# MCU.net
KiCad netlist of a schematic drawn in Altium Designer
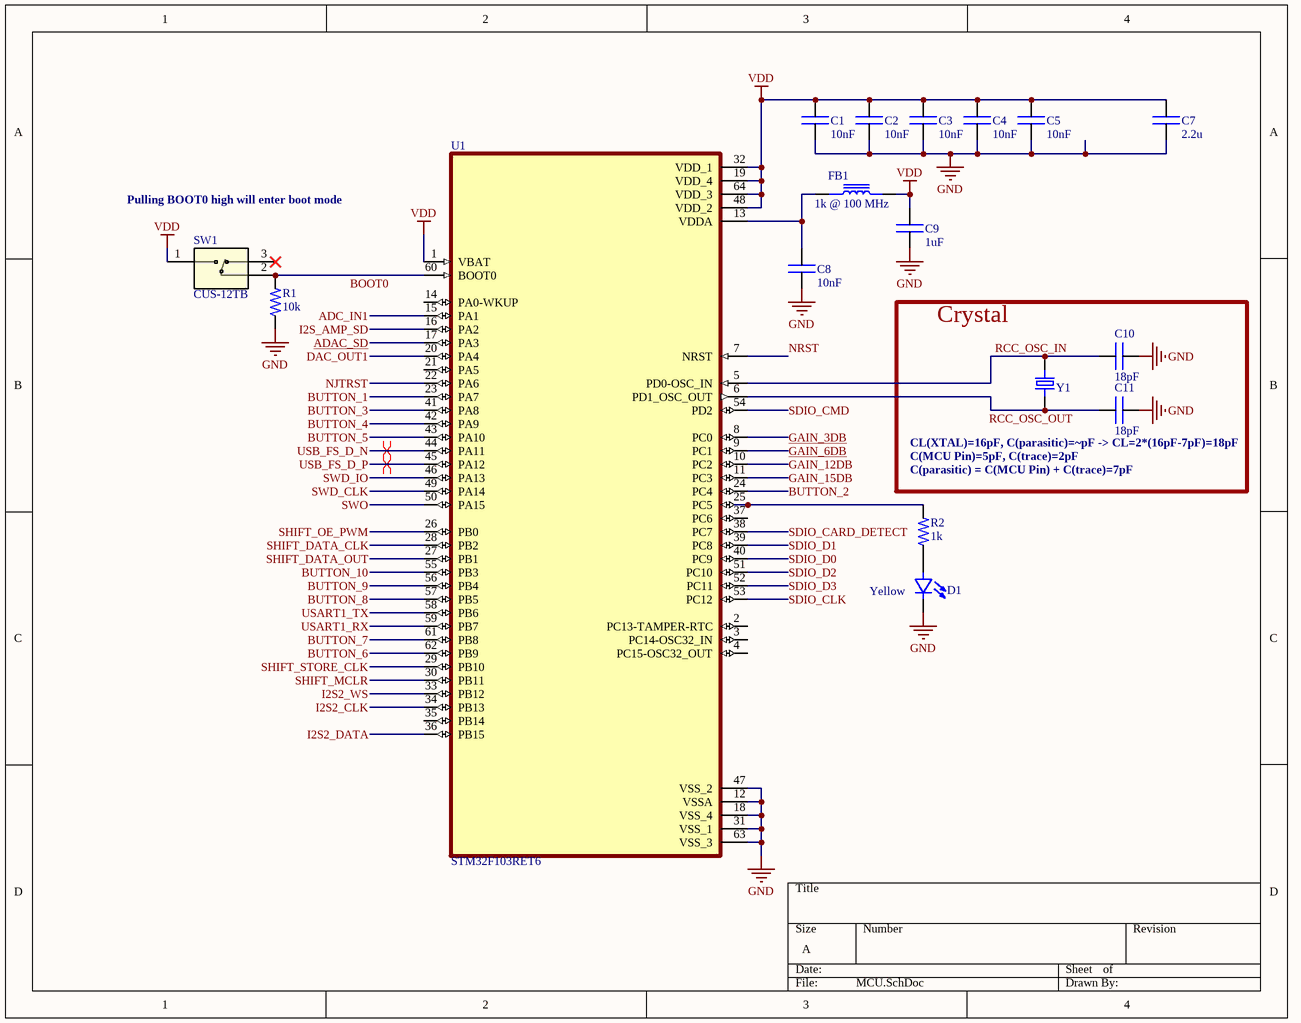
[diagram p0: MCU.SchDoc]

(export (version "E")
  (design (tool "Eeschema 10.0.6"))
  (components
    (comp (ref "C1")
      (value "10nF")
      (footprint "Christmas-2023_Soundboard:0603-CAP")
      (description "Capaicitor")
      (fields (field (name "Comment") "CAP"))
      (libsource (lib "Christmas-2023_Soundboard") (part "CAP"))
    )
    (comp (ref "C2")
      (value "10nF")
      (footprint "Christmas-2023_Soundboard:0603-CAP")
      (description "Capaicitor")
      (fields (field (name "Comment") "CAP"))
      (libsource (lib "Christmas-2023_Soundboard") (part "CAP"))
    )
    (comp (ref "C3")
      (value "10nF")
      (footprint "Christmas-2023_Soundboard:0603-CAP")
      (description "Capaicitor")
      (fields (field (name "Comment") "CAP"))
      (libsource (lib "Christmas-2023_Soundboard") (part "CAP"))
    )
    (comp (ref "C4")
      (value "10nF")
      (footprint "Christmas-2023_Soundboard:0603-CAP")
      (description "Capaicitor")
      (fields (field (name "Comment") "CAP"))
      (libsource (lib "Christmas-2023_Soundboard") (part "CAP"))
    )
    (comp (ref "C5")
      (value "10nF")
      (footprint "Christmas-2023_Soundboard:0603-CAP")
      (description "Capaicitor")
      (fields (field (name "Comment") "CAP"))
      (libsource (lib "Christmas-2023_Soundboard") (part "CAP"))
    )
    (comp (ref "C7")
      (value "2.2u")
      (footprint "Christmas-2023_Soundboard:0603-CAP")
      (description "Capaicitor")
      (fields (field (name "Comment") "CAP"))
      (libsource (lib "Christmas-2023_Soundboard") (part "CAP"))
    )
    (comp (ref "C8")
      (value "10nF")
      (footprint "Christmas-2023_Soundboard:0603-CAP")
      (description "Capaicitor")
      (fields (field (name "Comment") "CAP"))
      (libsource (lib "Christmas-2023_Soundboard") (part "CAP"))
    )
    (comp (ref "C9")
      (value "1uF")
      (footprint "Christmas-2023_Soundboard:0603-CAP")
      (description "Capaicitor")
      (fields (field (name "Comment") "CAP"))
      (libsource (lib "Christmas-2023_Soundboard") (part "CAP"))
    )
    (comp (ref "C10")
      (value "18pF")
      (footprint "Christmas-2023_Soundboard:0603-CAP")
      (description "Capaicitor")
      (fields (field (name "Comment") "CAP"))
      (libsource (lib "Christmas-2023_Soundboard") (part "CAP"))
    )
    (comp (ref "C11")
      (value "18pF")
      (footprint "Christmas-2023_Soundboard:0603-CAP")
      (description "Capaicitor")
      (fields (field (name "Comment") "CAP"))
      (libsource (lib "Christmas-2023_Soundboard") (part "CAP"))
    )
    (comp (ref "D1")
      (value "LED - single")
      (footprint "Christmas-2023_Soundboard:0603-LED")
      (description "LED")
      (fields (field (name "COLOR") "Yellow") (field (name "MFR") "MEIHUA"))
      (libsource (lib "Christmas-2023_Soundboard") (part "LED - single"))
    )
    (comp (ref "FB1")
      (value "1k @ 100 MHz")
      (footprint "Christmas-2023_Soundboard:0603-FB")
      (fields (field (name "MFR") "TDK"))
      (libsource (lib "Christmas-2023_Soundboard") (part "FERRITE BEAD"))
    )
    (comp (ref "R1")
      (value "10k")
      (footprint "Christmas-2023_Soundboard:0603-RES")
      (description "Resistor")
      (fields (field (name "Comment") "RES"))
      (libsource (lib "Christmas-2023_Soundboard") (part "RES"))
    )
    (comp (ref "R2")
      (value "1k")
      (footprint "Christmas-2023_Soundboard:0603-RES")
      (description "Resistor")
      (fields (field (name "Comment") "RES"))
      (libsource (lib "Christmas-2023_Soundboard") (part "RES"))
    )
    (comp (ref "SW1")
      (value "CUS-12TB")
      (footprint "Christmas-2023_Soundboard:SSSS811101")
      (description "JLC Alternate:\r\nSSSS811101")
      (fields (field (name "MFR") "ALPSALPINE"))
      (libsource (lib "Christmas-2023_Soundboard") (part "SPDT SLIDE SWITCH"))
    )
    (comp (ref "U1")
      (value "STM32F103RET6")
      (footprint "Christmas-2023_Soundboard:LQFP-64")
      (fields (field (name "MFR") "STMicroelectronics"))
      (libsource (lib "Christmas-2023_Soundboard") (part "STM32F103RET6"))
    )
    (comp (ref "Y1")
      (value "SX5B12.000F1620F30")
      (footprint "Christmas-2023_Soundboard:SMD5032-4P")
      (description "SMD Tuning Fork Crystal")
      (fields (field (name "MFR") "Shenzhen SCTF Elec"))
      (libsource (lib "Christmas-2023_Soundboard") (part "XTAL-OSC_JLC"))
    )
  )
  (nets
    (net (code "1") (name "/ADAC_SD") (class "Default")
      (node (ref "U1") (pin "17") (pinfunction "PA3_17") (pintype "bidirectional"))
    )
    (net (code "2") (name "/ADC_IN1") (class "Default")
      (node (ref "U1") (pin "15") (pinfunction "PA1_15") (pintype "bidirectional"))
    )
    (net (code "3") (name "/BOOT0") (class "Default")
      (node (ref "R1") (pin "2") (pinfunction "2_2") (pintype "passive"))
      (node (ref "SW1") (pin "2") (pinfunction "2_2") (pintype "passive"))
      (node (ref "U1") (pin "60") (pinfunction "BOOT0_60") (pintype "input"))
    )
    (net (code "4") (name "/BUTTON_1") (class "Default")
      (node (ref "U1") (pin "23") (pinfunction "PA7_23") (pintype "bidirectional"))
    )
    (net (code "5") (name "/BUTTON_2") (class "Default")
      (node (ref "U1") (pin "24") (pinfunction "PC4_24") (pintype "bidirectional"))
    )
    (net (code "6") (name "/BUTTON_3") (class "Default")
      (node (ref "U1") (pin "41") (pinfunction "PA8_41") (pintype "bidirectional"))
    )
    (net (code "7") (name "/BUTTON_4") (class "Default")
      (node (ref "U1") (pin "42") (pinfunction "PA9_42") (pintype "bidirectional"))
    )
    (net (code "8") (name "/BUTTON_5") (class "Default")
      (node (ref "U1") (pin "43") (pinfunction "PA10_43") (pintype "bidirectional"))
    )
    (net (code "9") (name "/BUTTON_6") (class "Default")
      (node (ref "U1") (pin "62") (pinfunction "PB9_62") (pintype "bidirectional"))
    )
    (net (code "10") (name "/BUTTON_7") (class "Default")
      (node (ref "U1") (pin "61") (pinfunction "PB8_61") (pintype "bidirectional"))
    )
    (net (code "11") (name "/BUTTON_8") (class "Default")
      (node (ref "U1") (pin "57") (pinfunction "PB5_57") (pintype "bidirectional"))
    )
    (net (code "12") (name "/BUTTON_9") (class "Default")
      (node (ref "U1") (pin "56") (pinfunction "PB4_56") (pintype "bidirectional"))
    )
    (net (code "13") (name "/BUTTON_10") (class "Default")
      (node (ref "U1") (pin "55") (pinfunction "PB3_55") (pintype "bidirectional"))
    )
    (net (code "14") (name "/DAC_OUT1") (class "Default")
      (node (ref "U1") (pin "20") (pinfunction "PA4_20") (pintype "bidirectional"))
    )
    (net (code "15") (name "/GAIN_3DB") (class "Default")
      (node (ref "U1") (pin "8") (pinfunction "PC0_8") (pintype "bidirectional"))
    )
    (net (code "16") (name "/GAIN_6DB") (class "Default")
      (node (ref "U1") (pin "9") (pinfunction "PC1_9") (pintype "bidirectional"))
    )
    (net (code "17") (name "/GAIN_12DB") (class "Default")
      (node (ref "U1") (pin "10") (pinfunction "PC2_10") (pintype "bidirectional"))
    )
    (net (code "18") (name "/GAIN_15DB") (class "Default")
      (node (ref "U1") (pin "11") (pinfunction "PC3_11") (pintype "bidirectional"))
    )
    (net (code "19") (name "/I2S2_CLK") (class "Default")
      (node (ref "U1") (pin "34") (pinfunction "PB13_34") (pintype "bidirectional"))
    )
    (net (code "20") (name "/I2S2_DATA") (class "Default")
      (node (ref "U1") (pin "36") (pinfunction "PB15_36") (pintype "bidirectional"))
    )
    (net (code "21") (name "/I2S2_WS") (class "Default")
      (node (ref "U1") (pin "33") (pinfunction "PB12_33") (pintype "bidirectional"))
    )
    (net (code "22") (name "/I2S_AMP_SD") (class "Default")
      (node (ref "U1") (pin "16") (pinfunction "PA2_16") (pintype "bidirectional"))
    )
    (net (code "23") (name "/NJTRST") (class "Default")
      (node (ref "U1") (pin "22") (pinfunction "PA6_22") (pintype "bidirectional"))
    )
    (net (code "24") (name "/NRST") (class "Default")
      (node (ref "U1") (pin "7") (pinfunction "NRST_7") (pintype "input"))
    )
    (net (code "25") (name "/RCC_OSC_IN") (class "Default")
      (node (ref "C10") (pin "1") (pinfunction "1_1") (pintype "passive"))
      (node (ref "U1") (pin "5") (pinfunction "PD0-OSC_IN_5") (pintype "input"))
      (node (ref "Y1") (pin "1") (pinfunction "1_1") (pintype "passive"))
    )
    (net (code "26") (name "/RCC_OSC_OUT") (class "Default")
      (node (ref "C11") (pin "1") (pinfunction "1_1") (pintype "passive"))
      (node (ref "U1") (pin "6") (pinfunction "PD1_OSC_OUT_6") (pintype "output"))
      (node (ref "Y1") (pin "2") (pinfunction "2_2") (pintype "passive"))
    )
    (net (code "27") (name "/SDIO_CARD_DETECT") (class "Default")
      (node (ref "U1") (pin "38") (pinfunction "PC7_38") (pintype "bidirectional"))
    )
    (net (code "28") (name "/SDIO_CLK") (class "Default")
      (node (ref "U1") (pin "53") (pinfunction "PC12_53") (pintype "bidirectional"))
    )
    (net (code "29") (name "/SDIO_CMD") (class "Default")
      (node (ref "U1") (pin "54") (pinfunction "PD2_54") (pintype "bidirectional"))
    )
    (net (code "30") (name "/SDIO_D0") (class "Default")
      (node (ref "U1") (pin "40") (pinfunction "PC9_40") (pintype "bidirectional"))
    )
    (net (code "31") (name "/SDIO_D1") (class "Default")
      (node (ref "U1") (pin "39") (pinfunction "PC8_39") (pintype "bidirectional"))
    )
    (net (code "32") (name "/SDIO_D2") (class "Default")
      (node (ref "U1") (pin "51") (pinfunction "PC10_51") (pintype "bidirectional"))
    )
    (net (code "33") (name "/SDIO_D3") (class "Default")
      (node (ref "U1") (pin "52") (pinfunction "PC11_52") (pintype "bidirectional"))
    )
    (net (code "34") (name "/SHIFT_DATA_CLK") (class "Default")
      (node (ref "U1") (pin "28") (pinfunction "PB2_28") (pintype "bidirectional"))
    )
    (net (code "35") (name "/SHIFT_DATA_OUT") (class "Default")
      (node (ref "U1") (pin "27") (pinfunction "PB1_27") (pintype "bidirectional"))
    )
    (net (code "36") (name "/SHIFT_MCLR") (class "Default")
      (node (ref "U1") (pin "30") (pinfunction "PB11_30") (pintype "bidirectional"))
    )
    (net (code "37") (name "/SHIFT_OE_PWM") (class "Default")
      (node (ref "U1") (pin "26") (pinfunction "PB0_26") (pintype "bidirectional"))
    )
    (net (code "38") (name "/SHIFT_STORE_CLK") (class "Default")
      (node (ref "U1") (pin "29") (pinfunction "PB10_29") (pintype "bidirectional"))
    )
    (net (code "39") (name "/SWD_CLK") (class "Default")
      (node (ref "U1") (pin "49") (pinfunction "PA14_49") (pintype "bidirectional"))
    )
    (net (code "40") (name "/SWD_IO") (class "Default")
      (node (ref "U1") (pin "46") (pinfunction "PA13_46") (pintype "bidirectional"))
    )
    (net (code "41") (name "/SWO") (class "Default")
      (node (ref "U1") (pin "50") (pinfunction "PA15_50") (pintype "bidirectional"))
    )
    (net (code "42") (name "/USART1_RX") (class "Default")
      (node (ref "U1") (pin "59") (pinfunction "PB7_59") (pintype "bidirectional"))
    )
    (net (code "43") (name "/USART1_TX") (class "Default")
      (node (ref "U1") (pin "58") (pinfunction "PB6_58") (pintype "bidirectional"))
    )
    (net (code "44") (name "/USB_FS_D_N") (class "Default")
      (node (ref "U1") (pin "44") (pinfunction "PA11_44") (pintype "bidirectional"))
    )
    (net (code "45") (name "/USB_FS_D_P") (class "Default")
      (node (ref "U1") (pin "45") (pinfunction "PA12_45") (pintype "bidirectional"))
    )
    (net (code "46") (name "GND") (class "Default")
      (node (ref "C1") (pin "1") (pinfunction "1_1") (pintype "passive"))
      (node (ref "C10") (pin "2") (pinfunction "2_2") (pintype "passive"))
      (node (ref "C11") (pin "2") (pinfunction "2_2") (pintype "passive"))
      (node (ref "C2") (pin "1") (pinfunction "1_1") (pintype "passive"))
      (node (ref "C3") (pin "1") (pinfunction "1_1") (pintype "passive"))
      (node (ref "C4") (pin "1") (pinfunction "1_1") (pintype "passive"))
      (node (ref "C5") (pin "1") (pinfunction "1_1") (pintype "passive"))
      (node (ref "C7") (pin "1") (pinfunction "1_1") (pintype "passive"))
      (node (ref "C8") (pin "1") (pinfunction "1_1") (pintype "passive"))
      (node (ref "C9") (pin "1") (pinfunction "1_1") (pintype "passive"))
      (node (ref "D1") (pin "2") (pinfunction "C_2") (pintype "passive"))
      (node (ref "R1") (pin "1") (pinfunction "1_1") (pintype "passive"))
      (node (ref "U1") (pin "12") (pinfunction "VSSA_12") (pintype "power_in"))
      (node (ref "U1") (pin "18") (pinfunction "VSS_4_18") (pintype "power_in"))
      (node (ref "U1") (pin "31") (pinfunction "VSS_1_31") (pintype "power_in"))
      (node (ref "U1") (pin "47") (pinfunction "VSS_2_47") (pintype "power_in"))
      (node (ref "U1") (pin "63") (pinfunction "VSS_3_63") (pintype "power_in"))
    )
    (net (code "47") (name "Net-(D1-A)") (class "Default")
      (node (ref "D1") (pin "1") (pinfunction "A_1") (pintype "passive"))
      (node (ref "R2") (pin "1") (pinfunction "1_1") (pintype "passive"))
    )
    (net (code "48") (name "Net-(U1-PC5)") (class "Default")
      (node (ref "R2") (pin "2") (pinfunction "2_2") (pintype "passive"))
      (node (ref "U1") (pin "25") (pinfunction "PC5_25") (pintype "bidirectional"))
    )
    (net (code "49") (name "Net-(U1-VDDA)") (class "Default")
      (node (ref "C8") (pin "2") (pinfunction "2_2") (pintype "passive"))
      (node (ref "FB1") (pin "1") (pinfunction "1_1") (pintype "passive"))
      (node (ref "U1") (pin "13") (pinfunction "VDDA_13") (pintype "power_in"))
    )
    (net (code "50") (name "VDD") (class "Default")
      (node (ref "C1") (pin "2") (pinfunction "2_2") (pintype "passive"))
      (node (ref "C2") (pin "2") (pinfunction "2_2") (pintype "passive"))
      (node (ref "C3") (pin "2") (pinfunction "2_2") (pintype "passive"))
      (node (ref "C4") (pin "2") (pinfunction "2_2") (pintype "passive"))
      (node (ref "C5") (pin "2") (pinfunction "2_2") (pintype "passive"))
      (node (ref "C7") (pin "2") (pinfunction "2_2") (pintype "passive"))
      (node (ref "C9") (pin "2") (pinfunction "2_2") (pintype "passive"))
      (node (ref "FB1") (pin "2") (pinfunction "2_2") (pintype "passive"))
      (node (ref "SW1") (pin "1") (pinfunction "1_1") (pintype "passive"))
      (node (ref "U1") (pin "1") (pinfunction "VBAT_1") (pintype "input"))
      (node (ref "U1") (pin "19") (pinfunction "VDD_4_19") (pintype "power_in"))
      (node (ref "U1") (pin "32") (pinfunction "VDD_1_32") (pintype "power_in"))
      (node (ref "U1") (pin "48") (pinfunction "VDD_2_48") (pintype "power_in"))
      (node (ref "U1") (pin "64") (pinfunction "VDD_3_64") (pintype "power_in"))
    )
    (net (code "51") (name "unconnected-(SW1-Pad3)") (class "Default")
      (node (ref "SW1") (pin "3") (pinfunction "3_3") (pintype "passive+no_connect"))
    )
    (net (code "52") (name "unconnected-(U1-PA0-WKUP-Pad14)") (class "Default")
      (node (ref "U1") (pin "14") (pinfunction "PA0-WKUP_14") (pintype "bidirectional"))
    )
    (net (code "53") (name "unconnected-(U1-PA5-Pad21)") (class "Default")
      (node (ref "U1") (pin "21") (pinfunction "PA5_21") (pintype "bidirectional"))
    )
    (net (code "54") (name "unconnected-(U1-PB14-Pad35)") (class "Default")
      (node (ref "U1") (pin "35") (pinfunction "PB14_35") (pintype "bidirectional"))
    )
    (net (code "55") (name "unconnected-(U1-PC6-Pad37)") (class "Default")
      (node (ref "U1") (pin "37") (pinfunction "PC6_37") (pintype "bidirectional"))
    )
    (net (code "56") (name "unconnected-(U1-PC13-TAMPER-RTC-Pad2)") (class "Default")
      (node (ref "U1") (pin "2") (pinfunction "PC13-TAMPER-RTC_2") (pintype "bidirectional"))
    )
    (net (code "57") (name "unconnected-(U1-PC14-OSC32_IN-Pad3)") (class "Default")
      (node (ref "U1") (pin "3") (pinfunction "PC14-OSC32_IN_3") (pintype "bidirectional"))
    )
    (net (code "58") (name "unconnected-(U1-PC15-OSC32_OUT-Pad4)") (class "Default")
      (node (ref "U1") (pin "4") (pinfunction "PC15-OSC32_OUT_4") (pintype "bidirectional"))
    )
  )
)
